# -15V.net
KiCad netlist of a schematic drawn in Altium Designer
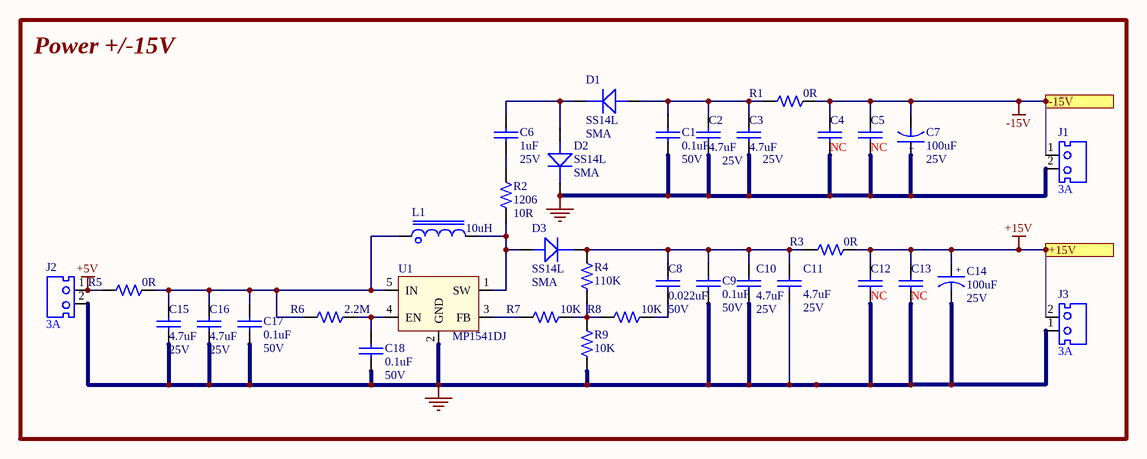
[diagram p0: +-15V.SchDoc]

(export (version "E")
  (design (tool "Eeschema 10.0.6"))
  (components
    (comp (ref "C1")
      (value "0.1uF")
      (footprint "CAPC0603-RW")
      (description "CAP X7R .10UF 50V +-10% 0603 WALSIN L")
      (fields
        (field (name "MFG") "WALSIN")
        (field (name "MFG PART") "0603B104K500")
        (field (name "VOLTAGE") "50V")
        (field (name "CREATE_NAME") "Nathan")
      )
      (libsource (lib "P-Capacitors") (part "CAP0603 0.1uF 50V 10%_X7R"))
    )
    (comp (ref "C2")
      (value "4.7uF")
      (footprint "CAPC0603-RW")
      (description "CAP X7R 4.7UF 25V +-10% 0603 WALSIN L")
      (fields
        (field (name "MFG") "WALSIN")
        (field (name "TOLERANCE") "10%")
        (field (name "VOLTAGE") "25V")
        (field (name "CREATE_NAME") "Nathan")
      )
      (libsource (lib "P-Capacitors") (part "CAP0603 4.7uF 25V 10%_X7R_WALSIN"))
    )
    (comp (ref "C3")
      (value "4.7uF")
      (footprint "CAPC0603-RW")
      (description "CAP X7R 4.7UF 25V +-10% 0603 WALSIN L")
      (fields
        (field (name "MFG") "WALSIN")
        (field (name "TOLERANCE") "10%")
        (field (name "VOLTAGE") "25V")
        (field (name "CREATE_NAME") "Nathan")
      )
      (libsource (lib "P-Capacitors") (part "CAP0603 4.7uF 25V 10%_X7R_WALSIN"))
    )
    (comp (ref "C4")
      (value "NC")
      (footprint "CAPC0603-RW")
      (fields (field (name "Comment") "T542024757408") (field (name "CREATE_NAME") "Tom"))
      (libsource (lib "Temporary") (part "CAP0603 NC"))
    )
    (comp (ref "C5")
      (value "NC")
      (footprint "CAPC0603-RW")
      (fields (field (name "Comment") "CAP0603 NC") (field (name "CREATE_NAME") "Tom"))
      (libsource (lib "Temporary") (part "CAP0603 NC"))
    )
    (comp (ref "C6")
      (value "1uF")
      (footprint "CAPC1206-RW")
      (description "GP CHIP CAP  1uF 25V 10%")
      (fields
        (field (name "TOLERANCE") "10%")
        (field (name "VOLTAGE") "25V")
        (field (name "Comment") "PZL456450-1050")
      )
      (libsource (lib "P-Capacitors") (part "CAPC1206 1uF 25V 10% - PZL456450-1050"))
    )
    (comp (ref "C7")
      (value "100uF")
      (footprint "CASE - D8")
      (description "E 100UF 25V +-20% 6.3X7. VEJ101M1E K")
      (fields
        (field (name "MFG") "LELON")
        (field (name "MFG PART") "VEJ101M1ETR-0607")
        (field (name "VOLTAGE") "25V")
        (field (name "CREATE_NAME") "Nathan")
      )
      (libsource (lib "P-Capacitors") (part "CAP E 100uF 25V 20% SMD_VEJ101M1ETR-0607"))
    )
    (comp (ref "C8")
      (value "0.022uF")
      (footprint "CAPC0603-RW")
      (description "GP CHIP CAP 0.022uF 50V 10%")
      (fields
        (field (name "TOLERANCE") "10%")
        (field (name "VOLTAGE") "50V")
        (field (name "Comment") "PXL456470-2230")
      )
      (libsource (lib "P-Capacitors") (part "CAP0603 0.022uF 50V 10%"))
    )
    (comp (ref "C9")
      (value "0.1uF")
      (footprint "CAPC0603-RW")
      (description "CAP X7R .10UF 50V +-10% 0603 WALSIN L")
      (fields
        (field (name "MFG") "WALSIN")
        (field (name "MFG PART") "0603B104K500")
        (field (name "VOLTAGE") "50V")
        (field (name "CREATE_NAME") "Nathan")
      )
      (libsource (lib "P-Capacitors") (part "CAP0603 0.1uF 50V 10%_X7R"))
    )
    (comp (ref "C10")
      (value "4.7uF")
      (footprint "CAPC0603-RW")
      (description "CAP X7R 4.7UF 25V +-10% 0603 WALSIN L")
      (fields
        (field (name "MFG") "WALSIN")
        (field (name "TOLERANCE") "10%")
        (field (name "VOLTAGE") "25V")
        (field (name "CREATE_NAME") "Nathan")
      )
      (libsource (lib "P-Capacitors") (part "CAP0603 4.7uF 25V 10%_X7R_WALSIN"))
    )
    (comp (ref "C11")
      (value "4.7uF")
      (footprint "CAPC0603-RW")
      (description "CAP X7R 4.7UF 25V +-10% 0603 WALSIN L")
      (fields
        (field (name "MFG") "WALSIN")
        (field (name "TOLERANCE") "10%")
        (field (name "VOLTAGE") "25V")
        (field (name "CREATE_NAME") "Nathan")
      )
      (libsource (lib "P-Capacitors") (part "CAP0603 4.7uF 25V 10%_X7R_WALSIN"))
    )
    (comp (ref "C12")
      (value "NC")
      (footprint "CAPC0603-RW")
      (fields (field (name "Comment") "T542024757408") (field (name "CREATE_NAME") "Tom"))
      (libsource (lib "Temporary") (part "CAP0603 NC"))
    )
    (comp (ref "C13")
      (value "NC")
      (footprint "CAPC0603-RW")
      (fields (field (name "Comment") "T542024757408") (field (name "CREATE_NAME") "Tom"))
      (libsource (lib "Temporary") (part "CAP0603 NC"))
    )
    (comp (ref "C14")
      (value "100uF")
      (footprint "CASE - D8")
      (description "E 100UF 25V +-20% 6.3X7. VEJ101M1E K")
      (fields
        (field (name "MFG") "LELON")
        (field (name "MFG PART") "VEJ101M1ETR-0607")
        (field (name "VOLTAGE") "25V")
        (field (name "CREATE_NAME") "Nathan")
      )
      (libsource (lib "") (part "CAP E 100uF 25V 20% SMD_VEJ101M1ETR-0607_1"))
    )
    (comp (ref "C15")
      (value "4.7uF")
      (footprint "CAPC0603-RW")
      (description "CAP X7R 4.7UF 25V +-10% 0603 WALSIN L")
      (fields
        (field (name "MFG") "WALSIN")
        (field (name "TOLERANCE") "10%")
        (field (name "VOLTAGE") "25V")
        (field (name "CREATE_NAME") "Nathan")
      )
      (libsource (lib "P-Capacitors") (part "CAP0603 4.7uF 25V 10%_X7R_WALSIN"))
    )
    (comp (ref "C16")
      (value "4.7uF")
      (footprint "CAPC0603-RW")
      (description "CAP X7R 4.7UF 25V +-10% 0603 WALSIN L")
      (fields
        (field (name "MFG") "WALSIN")
        (field (name "TOLERANCE") "10%")
        (field (name "VOLTAGE") "25V")
        (field (name "CREATE_NAME") "Nathan")
      )
      (libsource (lib "P-Capacitors") (part "CAP0603 4.7uF 25V 10%_X7R_WALSIN"))
    )
    (comp (ref "C17")
      (value "0.1uF")
      (footprint "CAPC0603-RW")
      (description "CAP X7R .10UF 50V +-10% 0603 WALSIN L")
      (fields
        (field (name "MFG") "WALSIN")
        (field (name "MFG PART") "0603B104K500")
        (field (name "VOLTAGE") "50V")
        (field (name "CREATE_NAME") "Nathan")
      )
      (libsource (lib "P-Capacitors") (part "CAP0603 0.1uF 50V 10%_X7R"))
    )
    (comp (ref "C18")
      (value "0.1uF")
      (footprint "CAPC0603-RW")
      (description "CAP X7R .10UF 50V +-10% 0603 WALSIN L")
      (fields
        (field (name "MFG") "WALSIN")
        (field (name "MFG PART") "0603B104K500")
        (field (name "VOLTAGE") "50V")
        (field (name "CREATE_NAME") "Nathan")
      )
      (libsource (lib "P-Capacitors") (part "CAP0603 0.1uF 50V 10%_X7R"))
    )
    (comp (ref "D1")
      (value "RCD100140-0010")
      (footprint "subSMA")
      (description "SMD Schottky Diode Sub SMA 1A 40V SS14L")
      (fields
        (field (name "MFG") "TSC")
        (field (name "MFG PART") "SS14L")
        (field (name "VOLTAGE") "40V")
        (field (name "PACKAGE") "SMA")
      )
      (libsource (lib "R-Semiconductors") (part "SS14L-TSC"))
    )
    (comp (ref "D2")
      (value "RCD100140-0010")
      (footprint "subSMA")
      (description "SMD Schottky Diode Sub SMA 1A 40V SS14L")
      (fields
        (field (name "MFG") "TSC")
        (field (name "MFG PART") "SS14L")
        (field (name "VOLTAGE") "40V")
        (field (name "PACKAGE") "SMA")
      )
      (libsource (lib "R-Semiconductors") (part "SS14L-TSC"))
    )
    (comp (ref "D3")
      (value "RCD100140-0010")
      (footprint "subSMA")
      (description "SMD Schottky Diode Sub SMA 1A 40V SS14L")
      (fields
        (field (name "MFG") "TSC")
        (field (name "MFG PART") "SS14L")
        (field (name "VOLTAGE") "40V")
        (field (name "PACKAGE") "SMA")
      )
      (libsource (lib "R-Semiconductors") (part "SS14L-TSC"))
    )
    (comp (ref "J1")
      (value "CCN250000-0102")
      (footprint "CONN 2P PH=2.5mm B2B-XH-A")
      (description "GP CONNECTOR B2B-XH-A 2 PIN G")
      (fields
        (field (name "MFG") "金瑞康")
        (field (name "MFG PART") "HAA250A-2A-WHITE")
        (field (name "CURRENT") "3A")
      )
      (libsource (lib "C-Connector") (part "CONN 2P PH=2.5mm B2B-XH-A"))
    )
    (comp (ref "J2")
      (value "CCN250000-0102")
      (footprint "CONN 2P PH=2.5mm B2B-XH-A")
      (description "GP CONNECTOR B2B-XH-A 2 PIN G")
      (fields
        (field (name "MFG") "金瑞康")
        (field (name "MFG PART") "HAA250A-2A-WHITE")
        (field (name "CURRENT") "3A")
      )
      (libsource (lib "C-Connector") (part "CONN 2P PH=2.5mm B2B-XH-A"))
    )
    (comp (ref "J3")
      (value "CCN250000-0102")
      (footprint "CONN 2P PH=2.5mm B2B-XH-A")
      (description "GP CONNECTOR B2B-XH-A 2 PIN G")
      (fields
        (field (name "MFG") "金瑞康")
        (field (name "MFG PART") "HAA250A-2A-WHITE")
        (field (name "CURRENT") "3A")
      )
      (libsource (lib "C-Connector") (part "CONN 2P PH=2.5mm B2B-XH-A"))
    )
    (comp (ref "L1")
      (value "10uH")
      (footprint "IND CKST0402")
      (description "10UH 2A 100K SMD CENKER CKST040 K")
      (fields
        (field (name "MFG") "CENKER")
        (field (name "MFG PART") "CKST0402-10uH/M")
        (field (name "CREATE_NAME") "Nathan")
      )
      (libsource (lib "S-Inductor") (part "IND 10uH CKST0402-10uH/M"))
    )
    (comp (ref "R1")
      (value "0R")
      (footprint "0805-RW")
      (description "CHIP 0 OHM 0 OHM 0 OHM 0805 WALSI L")
      (fields (field (name "POWER") "1/8W") (field (name "MFG") "WALSIN") (field (name "CREATE_NAME") "Tom"))
      (libsource (lib "Q-Resistors") (part "RES0805 1/8W  0 OHM_WALSIN"))
    )
    (comp (ref "R2")
      (value "10R")
      (footprint "1206-RW")
      (description "CHIP 10 OHM 100PPM +-5% 1206 WALS L")
      (fields
        (field (name "POWER") "1/4W")
        (field (name "MFG") "WALSIN (華新)")
        (field (name "PACKAGE") "1206")
      )
      (libsource (lib "Q-Resistors") (part "RES1206 1/4W 5% 10 OHM"))
    )
    (comp (ref "R3")
      (value "0R")
      (footprint "0805-RW")
      (description "CHIP 0 OHM 0 OHM 0 OHM 0805 WALSI L")
      (fields (field (name "POWER") "1/8W") (field (name "MFG") "WALSIN") (field (name "CREATE_NAME") "Tom"))
      (libsource (lib "Q-Resistors") (part "RES0805 1/8W  0 OHM_WALSIN"))
    )
    (comp (ref "R4")
      (value "110K")
      (footprint "0603-RW")
      (description "CHIP RES 110K OHM 1/10W 1% 0603")
      (fields (field (name "POWER") "1/10W") (field (name "Comment") "QCF011030-1103"))
      (libsource (lib "Q-Resistors") (part "RES0603 1/10W 1% 110K OHM"))
    )
    (comp (ref "R5")
      (value "0R")
      (footprint "0805-RW")
      (description "CHIP 0 OHM 0 OHM 0 OHM 0805 WALSI L")
      (fields (field (name "POWER") "1/8W") (field (name "MFG") "WALSIN") (field (name "CREATE_NAME") "Tom"))
      (libsource (lib "Q-Resistors") (part "RES0805 1/8W  0 OHM_WALSIN"))
    )
    (comp (ref "R6")
      (value "2.2M")
      (footprint "0603-RW")
      (description "GP CHIP RES. 2.2M OHM 1/10W 1% 0603")
      (fields (field (name "POWER") "1/10W") (field (name "Comment") "QCF011030-2204"))
      (libsource (lib "Q-Resistors") (part "RES0603 1/10W 1% 2.2M OHM"))
    )
    (comp (ref "R7")
      (value "10K")
      (footprint "0603-RW")
      (description "GP CHIP RES. 10K OHM 1/10W 1% 0603")
      (fields (field (name "POWER") "1/10W") (field (name "Comment") "QCF011030-1002"))
      (libsource (lib "Q-Resistors") (part "RES0603 1/10W 1% 10K OHM"))
    )
    (comp (ref "R8")
      (value "10K")
      (footprint "0603-RW")
      (description "GP CHIP RES. 10K OHM 1/10W 1% 0603")
      (fields (field (name "POWER") "1/10W") (field (name "Comment") "QCF011030-1002"))
      (libsource (lib "Q-Resistors") (part "RES0603 1/10W 1% 10K OHM"))
    )
    (comp (ref "R9")
      (value "10K")
      (footprint "0603-RW")
      (description "GP CHIP RES. 10K OHM 1/10W 1% 0603")
      (fields (field (name "POWER") "1/10W") (field (name "Comment") "QCF011030-1002"))
      (libsource (lib "Q-Resistors") (part "RES0603 1/10W 1% 10K OHM"))
    )
    (comp (ref "U1")
      (value "MP1541DJ")
      (footprint "SOT23-5 P.95")
      (fields
        (field (name "MFG") "MPS")
        (field (name "MFG PART") "MP1541DJ")
        (field (name "CREATE_NAME") "Tom")
      )
      (libsource (lib "Temporary-2") (part "MP1541DJ"))
    )
  )
  (nets
    (net (code "1") (name "+5V") (class "Default")
      (node (ref "J2") (pin "1") (pinfunction "1_1") (pintype "passive"))
      (node (ref "R5") (pin "1") (pinfunction "1_1") (pintype "passive"))
    )
    (net (code "2") (name "+15V") (class "Default")
      (node (ref "C12") (pin "1") (pinfunction "1_1") (pintype "passive"))
      (node (ref "C13") (pin "1") (pinfunction "1_1") (pintype "passive"))
      (node (ref "C14") (pin "1") (pinfunction "1_1") (pintype "passive"))
      (node (ref "J3") (pin "2") (pinfunction "2_2") (pintype "passive"))
      (node (ref "R3") (pin "2") (pinfunction "2_2") (pintype "passive"))
    )
    (net (code "3") (name "-15V") (class "Default")
      (node (ref "C4") (pin "1") (pinfunction "1_1") (pintype "passive"))
      (node (ref "C5") (pin "1") (pinfunction "1_1") (pintype "passive"))
      (node (ref "C7") (pin "2") (pinfunction "2_2") (pintype "passive"))
      (node (ref "J1") (pin "1") (pinfunction "1_1") (pintype "passive"))
      (node (ref "R1") (pin "2") (pinfunction "2_2") (pintype "passive"))
    )
    (net (code "4") (name "GND") (class "Default")
      (node (ref "C1") (pin "2") (pinfunction "2_2") (pintype "passive"))
      (node (ref "C10") (pin "2") (pinfunction "2_2") (pintype "passive"))
      (node (ref "C11") (pin "2") (pinfunction "2_2") (pintype "passive"))
      (node (ref "C12") (pin "2") (pinfunction "2_2") (pintype "passive"))
      (node (ref "C13") (pin "2") (pinfunction "2_2") (pintype "passive"))
      (node (ref "C14") (pin "2") (pinfunction "2_2") (pintype "passive"))
      (node (ref "C15") (pin "2") (pinfunction "2_2") (pintype "passive"))
      (node (ref "C16") (pin "2") (pinfunction "2_2") (pintype "passive"))
      (node (ref "C17") (pin "2") (pinfunction "2_2") (pintype "passive"))
      (node (ref "C18") (pin "2") (pinfunction "2_2") (pintype "passive"))
      (node (ref "C2") (pin "2") (pinfunction "2_2") (pintype "passive"))
      (node (ref "C3") (pin "2") (pinfunction "2_2") (pintype "passive"))
      (node (ref "C4") (pin "2") (pinfunction "2_2") (pintype "passive"))
      (node (ref "C5") (pin "2") (pinfunction "2_2") (pintype "passive"))
      (node (ref "C7") (pin "1") (pinfunction "1_1") (pintype "passive"))
      (node (ref "C9") (pin "2") (pinfunction "2_2") (pintype "passive"))
      (node (ref "D2") (pin "2") (pinfunction "K_2") (pintype "passive"))
      (node (ref "J1") (pin "2") (pinfunction "2_2") (pintype "passive"))
      (node (ref "J2") (pin "2") (pinfunction "2_2") (pintype "passive"))
      (node (ref "J3") (pin "1") (pinfunction "1_1") (pintype "passive"))
      (node (ref "R9") (pin "1") (pinfunction "1_1") (pintype "passive"))
      (node (ref "U1") (pin "2") (pinfunction "GND_2") (pintype "passive"))
    )
    (net (code "5") (name "Net-(C6-Pad2)") (class "Default")
      (node (ref "C6") (pin "2") (pinfunction "2_2") (pintype "passive"))
      (node (ref "R2") (pin "2") (pinfunction "2_2") (pintype "passive"))
    )
    (net (code "6") (name "Net-(C8-Pad2)") (class "Default")
      (node (ref "C8") (pin "2") (pinfunction "2_2") (pintype "passive"))
      (node (ref "R8") (pin "1") (pinfunction "1_1") (pintype "passive"))
    )
    (net (code "7") (name "Net-(D1-A)") (class "Default")
      (node (ref "C1") (pin "1") (pinfunction "1_1") (pintype "passive"))
      (node (ref "C2") (pin "1") (pinfunction "1_1") (pintype "passive"))
      (node (ref "C3") (pin "1") (pinfunction "1_1") (pintype "passive"))
      (node (ref "D1") (pin "1") (pinfunction "A_1") (pintype "passive"))
      (node (ref "R1") (pin "1") (pinfunction "1_1") (pintype "passive"))
    )
    (net (code "8") (name "Net-(D1-K)") (class "Default")
      (node (ref "C6") (pin "1") (pinfunction "1_1") (pintype "passive"))
      (node (ref "D1") (pin "2") (pinfunction "K_2") (pintype "passive"))
      (node (ref "D2") (pin "1") (pinfunction "A_1") (pintype "passive"))
    )
    (net (code "9") (name "Net-(D3-A)") (class "Default")
      (node (ref "D3") (pin "1") (pinfunction "A_1") (pintype "passive"))
      (node (ref "L1") (pin "2") (pinfunction "2_2") (pintype "passive"))
      (node (ref "R2") (pin "1") (pinfunction "1_1") (pintype "passive"))
      (node (ref "U1") (pin "1") (pinfunction "SW_1") (pintype "passive"))
    )
    (net (code "10") (name "Net-(D3-K)") (class "Default")
      (node (ref "C10") (pin "1") (pinfunction "1_1") (pintype "passive"))
      (node (ref "C11") (pin "1") (pinfunction "1_1") (pintype "passive"))
      (node (ref "C8") (pin "1") (pinfunction "1_1") (pintype "passive"))
      (node (ref "C9") (pin "1") (pinfunction "1_1") (pintype "passive"))
      (node (ref "D3") (pin "2") (pinfunction "K_2") (pintype "passive"))
      (node (ref "R3") (pin "1") (pinfunction "1_1") (pintype "passive"))
      (node (ref "R4") (pin "2") (pinfunction "2_2") (pintype "passive"))
    )
    (net (code "11") (name "Net-(R4-Pad1)") (class "Default")
      (node (ref "R4") (pin "1") (pinfunction "1_1") (pintype "passive"))
      (node (ref "R7") (pin "1") (pinfunction "1_1") (pintype "passive"))
      (node (ref "R8") (pin "2") (pinfunction "2_2") (pintype "passive"))
      (node (ref "R9") (pin "2") (pinfunction "2_2") (pintype "passive"))
    )
    (net (code "12") (name "Net-(U1-EN)") (class "Default")
      (node (ref "C18") (pin "1") (pinfunction "1_1") (pintype "passive"))
      (node (ref "R6") (pin "1") (pinfunction "1_1") (pintype "passive"))
      (node (ref "U1") (pin "4") (pinfunction "EN_4") (pintype "passive"))
    )
    (net (code "13") (name "Net-(U1-FB)") (class "Default")
      (node (ref "R7") (pin "2") (pinfunction "2_2") (pintype "passive"))
      (node (ref "U1") (pin "3") (pinfunction "FB_3") (pintype "passive"))
    )
    (net (code "14") (name "Net-(U1-IN)") (class "Default")
      (node (ref "C15") (pin "1") (pinfunction "1_1") (pintype "passive"))
      (node (ref "C16") (pin "1") (pinfunction "1_1") (pintype "passive"))
      (node (ref "C17") (pin "1") (pinfunction "1_1") (pintype "passive"))
      (node (ref "L1") (pin "1") (pinfunction "1_1") (pintype "passive"))
      (node (ref "R5") (pin "2") (pinfunction "2_2") (pintype "passive"))
      (node (ref "R6") (pin "2") (pinfunction "2_2") (pintype "passive"))
      (node (ref "U1") (pin "5") (pinfunction "IN_5") (pintype "passive"))
    )
  )
)
